# Power.net
KiCad netlist of a schematic drawn in Altium Designer
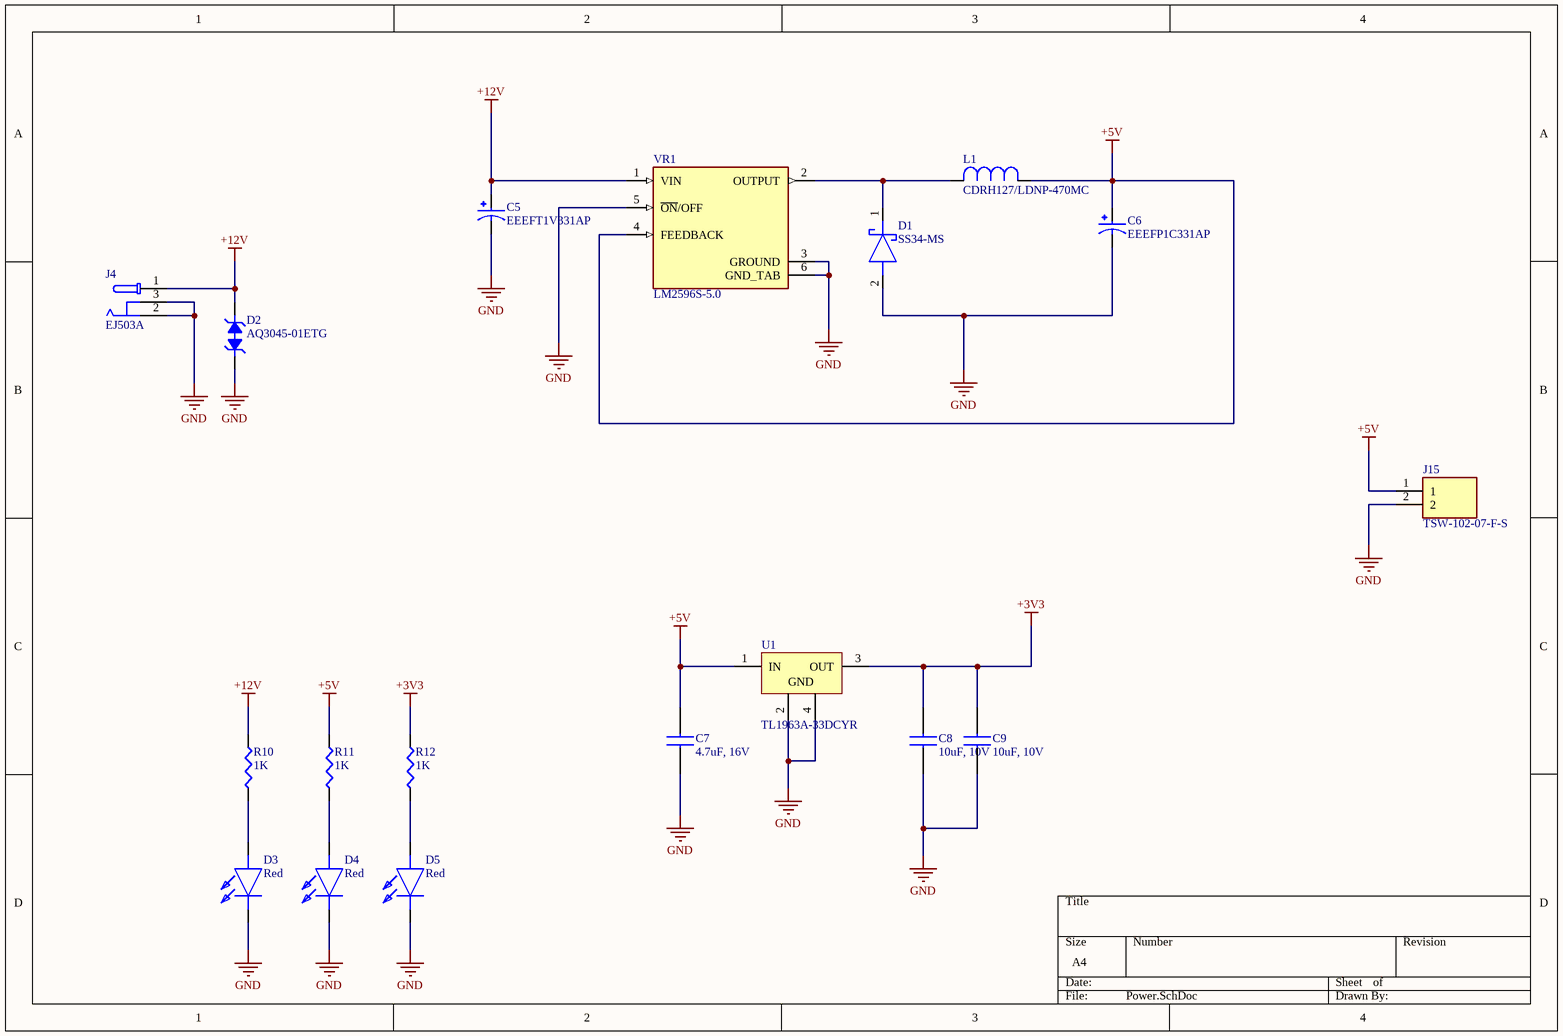
[diagram p0: Power.SchDoc]

(export (version "E")
  (design (tool "Eeschema 10.0.6"))
  (components
    (comp (ref "C5")
      (value "EEEFT1V331AP")
      (footprint "CAP_EEEFT1V331AP")
      (description "CAP ALUM 330UF 20% 35V SMD")
      (fields (field (name "MF") "Panasonic Electronic") (field (name "MP") "EEE-FT1V331AP"))
      (libsource (lib "SchlibpolyESP") (part "EEEFT1V331AP"))
    )
    (comp (ref "C6")
      (value "EEEFP1C331AP")
      (footprint "CAP_EEEFP1C331AP")
      (description "CAP ALUM 330UF 20% 16V SMD")
      (fields (field (name "MF") "Panasonic Electronic") (field (name "MP") "EEE-FP1C331AP"))
      (libsource (lib "SchlibpolyESP") (part "EEEFP1C331AP"))
    )
    (comp (ref "C7")
      (value "4.7uF, 16V")
      (footprint "SamacSys:CAPC1608X90N")
      (description "CAP CER 4,7UF 16V X5R 0603")
      (fields
        (field (name "MANUFACTURER_PART_NUMBER") "CL10A475KO8NNNC")
        (field (name "MOUSER PART NUMBER") "187-CL10A106MP8NNNC")
      )
      (libsource (lib "SchlibpolyESP") (part "CL10A475KO8NNNC"))
    )
    (comp (ref "C8")
      (value "10uF, 10V")
      (footprint "SamacSys:CAPC1608X90N")
      (description "CAP CER 10UF 10V X5R 0603")
      (fields
        (field (name "MANUFACTURER_PART_NUMBER") "CL10A106MP8NNNC")
        (field (name "MOUSER PART NUMBER") "187-CL10A106MP8NNNC")
      )
      (libsource (lib "SchlibpolyESP") (part "CL10A106MP8NNNC"))
    )
    (comp (ref "C9")
      (value "10uF, 10V")
      (footprint "SamacSys:CAPC1608X90N")
      (description "CAP CER 10UF 10V X5R 0603")
      (fields
        (field (name "MANUFACTURER_PART_NUMBER") "CL10A106MP8NNNC")
        (field (name "MOUSER PART NUMBER") "187-CL10A106MP8NNNC")
      )
      (libsource (lib "SchlibpolyESP") (part "CL10A106MP8NNNC"))
    )
    (comp (ref "D1")
      (value "SS34-MS")
      (footprint "SamacSys:DIOM5127X241N")
      (description "Schottky Diode")
      (libsource (lib "SchlibPoly") (part "SS34-MS"))
    )
    (comp (ref "D2")
      (value "AQ3045-01ETG")
      (footprint "SOD882")
      (description "TVS DIODE 5.3VWM 12VC SOD882")
      (fields (field (name "MANUFACTURER") "Littelfuse") (field (name "LCSC PART NUMBER") "C3710326"))
      (libsource (lib "SchlibPoly") (part "AQ3045-01ETG"))
    )
    (comp (ref "D3")
      (value "Red")
      (footprint "SamacSys:LEDC1608X90N")
      (description "Red LED 0603 (1608 Metric)")
      (fields
        (field (name "MANUFACTURER_PART_NUMBER") "HSMG-C190")
        (field (name "MOUSER PART NUMBER") "630-HSMG-C190")
      )
      (libsource (lib "SchlibpolyESP") (part "HSMS-C190"))
    )
    (comp (ref "D4")
      (value "Red")
      (footprint "SamacSys:LEDC1608X90N")
      (description "Red LED 0603 (1608 Metric)")
      (fields
        (field (name "MANUFACTURER_PART_NUMBER") "HSMG-C190")
        (field (name "MOUSER PART NUMBER") "630-HSMG-C190")
      )
      (libsource (lib "SchlibpolyESP") (part "HSMS-C190"))
    )
    (comp (ref "D5")
      (value "Red")
      (footprint "SamacSys:LEDC1608X90N")
      (description "Red LED 0603 (1608 Metric)")
      (fields
        (field (name "MANUFACTURER_PART_NUMBER") "HSMG-C190")
        (field (name "MOUSER PART NUMBER") "630-HSMG-C190")
      )
      (libsource (lib "SchlibpolyESP") (part "HSMS-C190"))
    )
    (comp (ref "J4")
      (value "EJ503A")
      (footprint "MPD_EJ503A")
      (description "Power Barrel Connector Jack 2.10mm ID (0.083), 5.50mm OD (0.217) Through Hole, Right Angle")
      (fields (field (name "MF") "MPD"))
      (libsource (lib "SchlibPoly") (part "EJ503A"))
    )
    (comp (ref "J15")
      (value "TSW-102-07-F-S")
      (footprint "SamacSys:TSW-102-XX-YY-S")
      (description "Connector")
      (fields (field (name "MOUSER PART NUMBER") "200-TSW10207FS"))
      (libsource (lib "SchlibpolyESP") (part "TSW-102-07-F-S"))
    )
    (comp (ref "L1")
      (value "CDRH127/LDNP-470MC")
      (footprint "IND_CDRH127/LDNP-470MC_SUM")
      (description "Inductor Power Shielded Drum Core 47uH 20% 1KHz Ferrite 4.1A 0.078Ohm DCR T/R")
      (fields (field (name "MF") "Sumida Corporation"))
      (libsource (lib "SchlibPoly") (part "CDRH127/LDNP-470MC"))
    )
    (comp (ref "R10")
      (value "1K")
      (footprint "RESC1607X60N")
      (description "Fixed Resistor, Thin Film, 0.1W, 1000ohm, 75V, 0.1% +/-Tol, 25ppm/Cel, Surface Mount, 0603")
      (fields
        (field (name "MANUFACTURER") "Yageo")
        (field (name "MANUFACTURER PART NUMBER") "RT0603BRD071KL")
      )
      (libsource (lib "SchlibpolyESP") (part "RT0603BRD071KL"))
    )
    (comp (ref "R11")
      (value "1K")
      (footprint "RESC1607X60N")
      (description "Fixed Resistor, Thin Film, 0.1W, 1000ohm, 75V, 0.1% +/-Tol, 25ppm/Cel, Surface Mount, 0603")
      (fields
        (field (name "MANUFACTURER") "Yageo")
        (field (name "MANUFACTURER PART NUMBER") "RT0603BRD071KL")
      )
      (libsource (lib "SchlibpolyESP") (part "RT0603BRD071KL"))
    )
    (comp (ref "R12")
      (value "1K")
      (footprint "RESC1607X60N")
      (description "Fixed Resistor, Thin Film, 0.1W, 1000ohm, 75V, 0.1% +/-Tol, 25ppm/Cel, Surface Mount, 0603")
      (fields
        (field (name "MANUFACTURER") "Yageo")
        (field (name "MANUFACTURER PART NUMBER") "RT0603BRD071KL")
      )
      (libsource (lib "SchlibpolyESP") (part "RT0603BRD071KL"))
    )
    (comp (ref "U1")
      (value "TL1963A-33DCYR")
      (footprint "DCY0004A_N")
      (description "IC REG LINEAR 3.3V 1.5A SOT223-4")
      (fields (field (name "MANUFACTURER") "Texas Instruments") (field (name "LCSC PART NUMBER") "C181262"))
      (libsource (lib "SchlibPoly") (part "TL1963A-33DCYR"))
    )
    (comp (ref "VR1")
      (value "LM2596S-5.0")
      (footprint "TO170P1524X483-6N")
      (description "SIMPLE SWITCHERÂ® 4.5V to 40V, 3A Low Component Count Step-Down Regulator")
      (fields (field (name "MF") "Texas Instruments") (field (name "MP") "LM2596S-5.0/NOPB"))
      (libsource (lib "SchlibPoly") (part "LM2596S-5.0"))
    )
  )
  (nets
    (net (code "1") (name "+3V3") (class "Default")
      (node (ref "C8") (pin "2") (pinfunction "2_2") (pintype "passive"))
      (node (ref "C9") (pin "2") (pinfunction "2_2") (pintype "passive"))
      (node (ref "R12") (pin "2") (pinfunction "2_2") (pintype "passive"))
      (node (ref "U1") (pin "3") (pinfunction "OUT_3") (pintype "power_in"))
    )
    (net (code "2") (name "+5V") (class "Default")
      (node (ref "C6") (pin "1") (pinfunction "1_1") (pintype "passive"))
      (node (ref "C7") (pin "2") (pinfunction "2_2") (pintype "passive"))
      (node (ref "J15") (pin "1") (pinfunction "1_1") (pintype "passive"))
      (node (ref "L1") (pin "1") (pinfunction "1_1") (pintype "passive"))
      (node (ref "R11") (pin "2") (pinfunction "2_2") (pintype "passive"))
      (node (ref "U1") (pin "1") (pinfunction "IN_1") (pintype "power_in"))
      (node (ref "VR1") (pin "4") (pinfunction "FEEDBACK_4") (pintype "input"))
    )
    (net (code "3") (name "+12V") (class "Default")
      (node (ref "C5") (pin "1") (pinfunction "1_1") (pintype "passive"))
      (node (ref "D2") (pin "2") (pinfunction "2_2") (pintype "passive"))
      (node (ref "J4") (pin "1") (pinfunction "1_1") (pintype "passive"))
      (node (ref "R10") (pin "2") (pinfunction "2_2") (pintype "passive"))
      (node (ref "VR1") (pin "1") (pinfunction "VIN_1") (pintype "input"))
    )
    (net (code "4") (name "GND") (class "Default")
      (node (ref "C5") (pin "2") (pinfunction "2_2") (pintype "passive"))
      (node (ref "C6") (pin "2") (pinfunction "2_2") (pintype "passive"))
      (node (ref "C7") (pin "1") (pinfunction "1_1") (pintype "passive"))
      (node (ref "C8") (pin "1") (pinfunction "1_1") (pintype "passive"))
      (node (ref "C9") (pin "1") (pinfunction "1_1") (pintype "passive"))
      (node (ref "D1") (pin "2") (pinfunction "A_2") (pintype "passive"))
      (node (ref "D2") (pin "1") (pinfunction "1_1") (pintype "passive"))
      (node (ref "D3") (pin "1") (pinfunction "K_1") (pintype "passive"))
      (node (ref "D4") (pin "1") (pinfunction "K_1") (pintype "passive"))
      (node (ref "D5") (pin "1") (pinfunction "K_1") (pintype "passive"))
      (node (ref "J15") (pin "2") (pinfunction "2_2") (pintype "passive"))
      (node (ref "J4") (pin "2") (pinfunction "2_2") (pintype "passive"))
      (node (ref "J4") (pin "3") (pinfunction "3_3") (pintype "passive"))
      (node (ref "U1") (pin "2") (pinfunction "GND_2") (pintype "power_in"))
      (node (ref "U1") (pin "4") (pinfunction "GND_4") (pintype "power_in"))
      (node (ref "VR1") (pin "3") (pinfunction "GROUND_3") (pintype "power_in"))
      (node (ref "VR1") (pin "5") (pinfunction "~{ON}/OFF_5") (pintype "input"))
      (node (ref "VR1") (pin "6") (pinfunction "GND_TAB_6") (pintype "power_in"))
    )
    (net (code "5") (name "Net-(D1-K)") (class "Default")
      (node (ref "D1") (pin "1") (pinfunction "K_1") (pintype "passive"))
      (node (ref "L1") (pin "2") (pinfunction "2_2") (pintype "passive"))
      (node (ref "VR1") (pin "2") (pinfunction "OUTPUT_2") (pintype "output"))
    )
    (net (code "6") (name "Net-(D3-A)") (class "Default")
      (node (ref "D3") (pin "2") (pinfunction "A_2") (pintype "passive"))
      (node (ref "R10") (pin "1") (pinfunction "1_1") (pintype "passive"))
    )
    (net (code "7") (name "Net-(D4-A)") (class "Default")
      (node (ref "D4") (pin "2") (pinfunction "A_2") (pintype "passive"))
      (node (ref "R11") (pin "1") (pinfunction "1_1") (pintype "passive"))
    )
    (net (code "8") (name "Net-(D5-A)") (class "Default")
      (node (ref "D5") (pin "2") (pinfunction "A_2") (pintype "passive"))
      (node (ref "R12") (pin "1") (pinfunction "1_1") (pintype "passive"))
    )
  )
)
